# amp-LNA-BFPxxxF.net
KiCad netlist of a schematic drawn in EAGLE
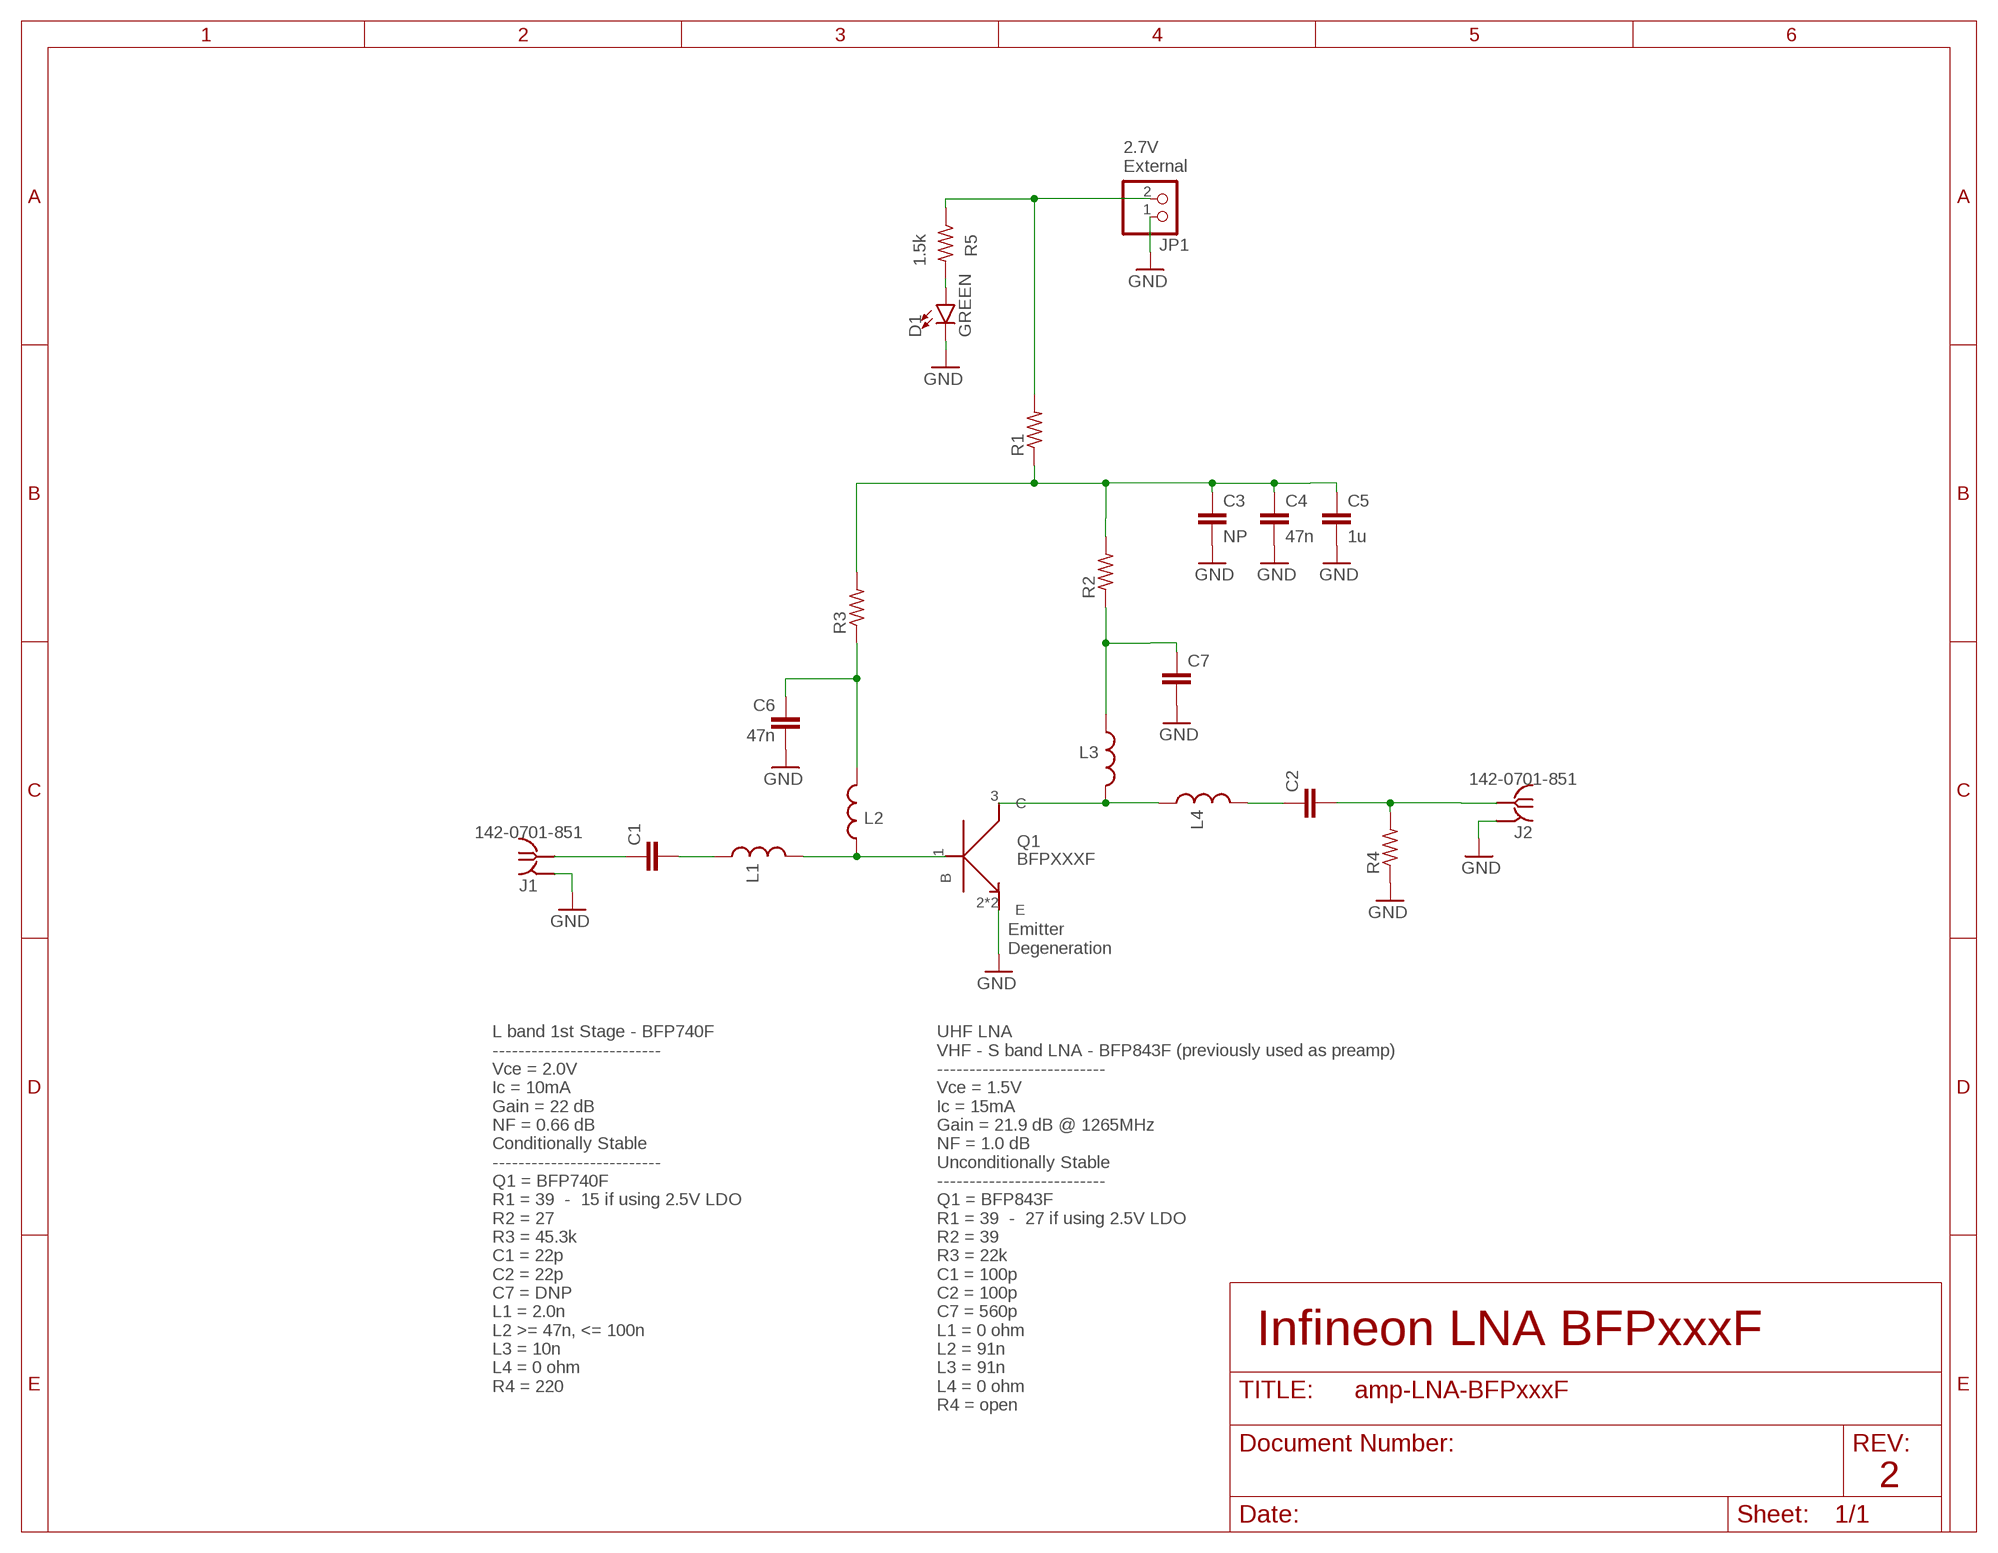
[diagram p0: schematic, sheet 1]

(export (version "E")
  (design (tool "Eeschema 10.0.6"))
  (components
    (comp (ref "C1")
      (value "C-EU0402-C-NOSILK")
      (footprint "eagle-import:.0402-C-NOSILK")
      (libsource (lib "eagle-import") (part "C-EU0402-C-NOSILK"))
    )
    (comp (ref "C2")
      (value "C-EU0402-C-NOSILK")
      (footprint "eagle-import:.0402-C-NOSILK")
      (libsource (lib "eagle-import") (part "C-EU0402-C-NOSILK"))
    )
    (comp (ref "C3")
      (value "NP")
      (footprint "eagle-import:.0603-C-NOSILK")
      (libsource (lib "eagle-import") (part "C-EU0603-C-NOSILK"))
    )
    (comp (ref "C4")
      (value "47n")
      (footprint "eagle-import:.0603-C-NOSILK")
      (libsource (lib "eagle-import") (part "C-EU0603-C-NOSILK"))
    )
    (comp (ref "C5")
      (value "1u")
      (footprint "eagle-import:.0603-C-NOSILK")
      (libsource (lib "eagle-import") (part "C-EU0603-C-NOSILK"))
    )
    (comp (ref "C6")
      (value "47n")
      (footprint "eagle-import:.0603-C-NOSILK")
      (libsource (lib "eagle-import") (part "C-EU0603-C-NOSILK"))
    )
    (comp (ref "C7")
      (value "C-EU0402-B-NOSILK")
      (footprint "eagle-import:.0402-B-NOSILK")
      (libsource (lib "eagle-import") (part "C-EU0402-B-NOSILK"))
    )
    (comp (ref "D1")
      (value "GREEN")
      (footprint "eagle-import:LED-0603")
      (libsource (lib "eagle-import") (part "LED-GREEN0603"))
    )
    (comp (ref "J1")
      (value "142-0701-851")
      (footprint "eagle-import:142-0701-851")
      (libsource (lib "eagle-import") (part "142-0701-851"))
    )
    (comp (ref "J2")
      (value "142-0701-851")
      (footprint "eagle-import:142-0701-851")
      (libsource (lib "eagle-import") (part "142-0701-851"))
    )
    (comp (ref "JP1")
      (value "PINHD-1X2")
      (footprint "eagle-import:1X02")
      (libsource (lib "eagle-import") (part "PINHD-1X2"))
    )
    (comp (ref "L1")
      (value "L-US0402-C-NOSILK")
      (footprint "eagle-import:.0402-C-NOSILK")
      (libsource (lib "eagle-import") (part "L-US0402-C-NOSILK"))
    )
    (comp (ref "L2")
      (value "L-US0603-C-NOSILK")
      (footprint "eagle-import:.0603-C-NOSILK")
      (libsource (lib "eagle-import") (part "L-US0603-C-NOSILK"))
    )
    (comp (ref "L3")
      (value "L-US0603-C-NOSILK")
      (footprint "eagle-import:.0603-C-NOSILK")
      (libsource (lib "eagle-import") (part "L-US0603-C-NOSILK"))
    )
    (comp (ref "L4")
      (value "L-US0402-C-NOSILK")
      (footprint "eagle-import:.0402-C-NOSILK")
      (libsource (lib "eagle-import") (part "L-US0402-C-NOSILK"))
    )
    (comp (ref "Q1")
      (value "BFPXXXF")
      (footprint "eagle-import:TSFP4")
      (libsource (lib "eagle-import") (part "BFPXXXF"))
    )
    (comp (ref "R1")
      (value "R-US_0603-C-NOSILK")
      (footprint "eagle-import:.0603-C-NOSILK")
      (libsource (lib "eagle-import") (part "R-US_0603-C-NOSILK"))
    )
    (comp (ref "R2")
      (value "R-US_0603-C-NOSILK")
      (footprint "eagle-import:.0603-C-NOSILK")
      (libsource (lib "eagle-import") (part "R-US_0603-C-NOSILK"))
    )
    (comp (ref "R3")
      (value "R-US_0603-C-NOSILK")
      (footprint "eagle-import:.0603-C-NOSILK")
      (libsource (lib "eagle-import") (part "R-US_0603-C-NOSILK"))
    )
    (comp (ref "R4")
      (value "R-US_0603-C-NOSILK")
      (footprint "eagle-import:.0603-C-NOSILK")
      (libsource (lib "eagle-import") (part "R-US_0603-C-NOSILK"))
    )
    (comp (ref "R5")
      (value "1.5k")
      (footprint "eagle-import:.0603-C-NOSILK")
      (libsource (lib "eagle-import") (part "R-US_0603-C-NOSILK"))
    )
  )
  (nets
    (net (code "1") (name "GND") (class "Default")
      (node (ref "C3") (pin "2") (pinfunction "2_2") (pintype "passive"))
      (node (ref "C4") (pin "2") (pinfunction "2_2") (pintype "passive"))
      (node (ref "C5") (pin "2") (pinfunction "2_2") (pintype "passive"))
      (node (ref "C6") (pin "2") (pinfunction "2_2") (pintype "passive"))
      (node (ref "C7") (pin "2") (pinfunction "2_2") (pintype "passive"))
      (node (ref "D1") (pin "C") (pinfunction "C_C") (pintype "passive"))
      (node (ref "J1") (pin "GND1") (pinfunction "GND_GND1") (pintype "bidirectional"))
      (node (ref "J1") (pin "GND2") (pinfunction "GND_GND2") (pintype "bidirectional"))
      (node (ref "J1") (pin "GND3") (pinfunction "GND_GND3") (pintype "bidirectional"))
      (node (ref "J1") (pin "GND4") (pinfunction "GND_GND4") (pintype "bidirectional"))
      (node (ref "J2") (pin "GND1") (pinfunction "GND_GND1") (pintype "bidirectional"))
      (node (ref "J2") (pin "GND2") (pinfunction "GND_GND2") (pintype "bidirectional"))
      (node (ref "J2") (pin "GND3") (pinfunction "GND_GND3") (pintype "bidirectional"))
      (node (ref "J2") (pin "GND4") (pinfunction "GND_GND4") (pintype "bidirectional"))
      (node (ref "JP1") (pin "1") (pinfunction "1_1") (pintype "passive"))
      (node (ref "Q1") (pin "2") (pinfunction "E_2") (pintype "power_in"))
      (node (ref "Q1") (pin "4") (pinfunction "E_4") (pintype "power_in"))
      (node (ref "R4") (pin "1") (pinfunction "1_1") (pintype "passive"))
    )
    (net (code "2") (name "Net-(C1-Pad2)") (class "Default")
      (node (ref "C1") (pin "2") (pinfunction "2_2") (pintype "passive"))
      (node (ref "L1") (pin "1") (pinfunction "1_1") (pintype "passive"))
    )
    (net (code "3") (name "Net-(C2-Pad1)") (class "Default")
      (node (ref "C2") (pin "1") (pinfunction "1_1") (pintype "passive"))
      (node (ref "L4") (pin "2") (pinfunction "2_2") (pintype "passive"))
    )
    (net (code "4") (name "Net-(C3-Pad1)") (class "Default")
      (node (ref "C3") (pin "1") (pinfunction "1_1") (pintype "passive"))
      (node (ref "C4") (pin "1") (pinfunction "1_1") (pintype "passive"))
      (node (ref "C5") (pin "1") (pinfunction "1_1") (pintype "passive"))
      (node (ref "R1") (pin "1") (pinfunction "1_1") (pintype "passive"))
      (node (ref "R2") (pin "2") (pinfunction "2_2") (pintype "passive"))
      (node (ref "R3") (pin "2") (pinfunction "2_2") (pintype "passive"))
    )
    (net (code "5") (name "Net-(C6-Pad1)") (class "Default")
      (node (ref "C6") (pin "1") (pinfunction "1_1") (pintype "passive"))
      (node (ref "L2") (pin "2") (pinfunction "2_2") (pintype "passive"))
      (node (ref "R3") (pin "1") (pinfunction "1_1") (pintype "passive"))
    )
    (net (code "6") (name "Net-(C7-Pad1)") (class "Default")
      (node (ref "C7") (pin "1") (pinfunction "1_1") (pintype "passive"))
      (node (ref "L3") (pin "1") (pinfunction "1_1") (pintype "passive"))
      (node (ref "R2") (pin "1") (pinfunction "1_1") (pintype "passive"))
    )
    (net (code "7") (name "Net-(D1-PadA)") (class "Default")
      (node (ref "D1") (pin "A") (pinfunction "A_A") (pintype "passive"))
      (node (ref "R5") (pin "2") (pinfunction "2_2") (pintype "passive"))
    )
    (net (code "8") (name "Net-(J1-RF)") (class "Default")
      (node (ref "C1") (pin "1") (pinfunction "1_1") (pintype "passive"))
      (node (ref "J1") (pin "RF1") (pinfunction "RF_RF1") (pintype "bidirectional"))
    )
    (net (code "9") (name "Net-(J2-RF)") (class "Default")
      (node (ref "C2") (pin "2") (pinfunction "2_2") (pintype "passive"))
      (node (ref "J2") (pin "RF1") (pinfunction "RF_RF1") (pintype "bidirectional"))
      (node (ref "R4") (pin "2") (pinfunction "2_2") (pintype "passive"))
    )
    (net (code "10") (name "Net-(JP1-Pad2)") (class "Default")
      (node (ref "JP1") (pin "2") (pinfunction "2_2") (pintype "passive"))
      (node (ref "R1") (pin "2") (pinfunction "2_2") (pintype "passive"))
      (node (ref "R5") (pin "1") (pinfunction "1_1") (pintype "passive"))
    )
    (net (code "11") (name "Net-(Q1-B)") (class "Default")
      (node (ref "L1") (pin "2") (pinfunction "2_2") (pintype "passive"))
      (node (ref "L2") (pin "1") (pinfunction "1_1") (pintype "passive"))
      (node (ref "Q1") (pin "1") (pinfunction "B_1") (pintype "input"))
    )
    (net (code "12") (name "Net-(Q1-C)") (class "Default")
      (node (ref "L3") (pin "2") (pinfunction "2_2") (pintype "passive"))
      (node (ref "L4") (pin "1") (pinfunction "1_1") (pintype "passive"))
      (node (ref "Q1") (pin "3") (pinfunction "C_3") (pintype "output"))
    )
  )
)
